# v0_1.net
KiCad netlist of a schematic drawn in EAGLE
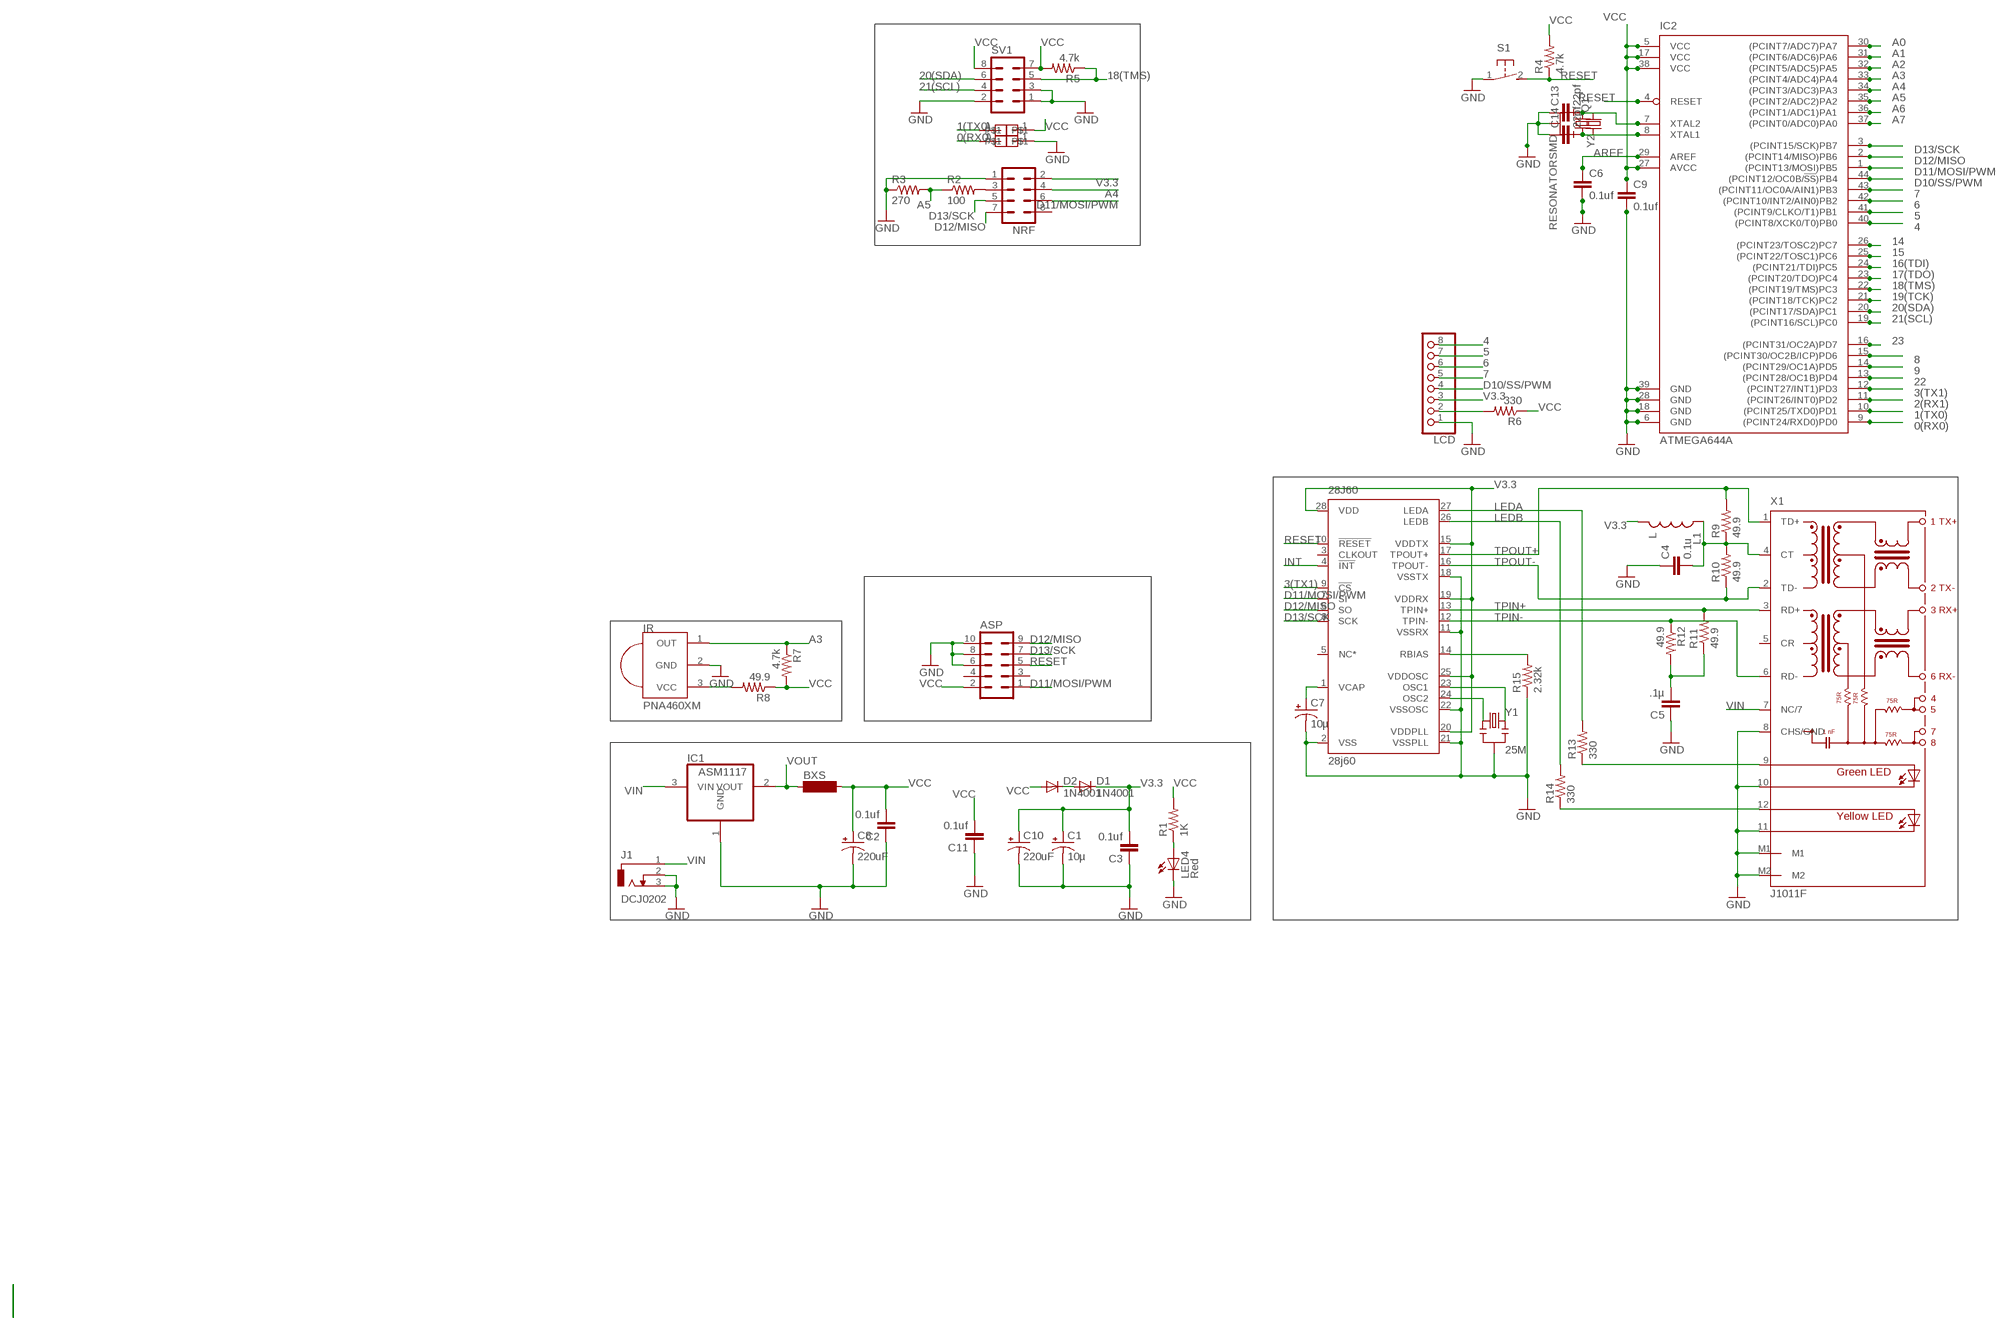
[diagram p0: schematic, sheet 1]

(export (version "E")
  (design (tool "Eeschema 10.0.6"))
  (components
    (comp (ref "28J60")
      (value "28j60")
      (footprint "eagle-import:SO28W")
      (libsource (lib "eagle-import") (part "ENC28J60SOIC"))
    )
    (comp (ref "ASP")
      (value "MA05-2")
      (footprint "eagle-import:MA05-2")
      (libsource (lib "eagle-import") (part "MA05-2"))
    )
    (comp (ref "BXS")
      (value "SM-1206")
      (footprint "eagle-import:SM-1206")
      (libsource (lib "eagle-import") (part "SM-1206"))
    )
    (comp (ref "C1")
      (value "10µ")
      (footprint "eagle-import:EIA3528")
      (libsource (lib "eagle-import") (part "CAP_POL3528"))
    )
    (comp (ref "C2")
      (value "0.1uf")
      (footprint "eagle-import:0603-CAP")
      (libsource (lib "eagle-import") (part "MY_CAP0603-CAP"))
    )
    (comp (ref "C3")
      (value "0.1uf")
      (footprint "eagle-import:0603-CAP")
      (libsource (lib "eagle-import") (part "MY_CAP0603-CAP"))
    )
    (comp (ref "C4")
      (value "0.1u")
      (footprint "eagle-import:0603-CAP")
      (libsource (lib "eagle-import") (part "CAP0603-CAP"))
    )
    (comp (ref "C5")
      (value ".1µ")
      (footprint "eagle-import:0603-CAP")
      (libsource (lib "eagle-import") (part "CAP0603-CAP"))
    )
    (comp (ref "C6")
      (value "0.1uf")
      (footprint "eagle-import:0603-CAP")
      (libsource (lib "eagle-import") (part "CAP0603-CAP"))
    )
    (comp (ref "C7")
      (value "10µ")
      (footprint "eagle-import:EIA3528")
      (libsource (lib "eagle-import") (part "CAP_POL3528"))
    )
    (comp (ref "C8")
      (value "220uF")
      (footprint "eagle-import:153CLV-0605")
      (libsource (lib "eagle-import") (part "CPOL-US153CLV-0605"))
    )
    (comp (ref "C9")
      (value "0.1uf")
      (footprint "eagle-import:0603-CAP")
      (libsource (lib "eagle-import") (part "CAP0603-CAP"))
    )
    (comp (ref "C10")
      (value "220uF")
      (footprint "eagle-import:153CLV-0605")
      (libsource (lib "eagle-import") (part "CPOL-US153CLV-0605"))
    )
    (comp (ref "C11")
      (value "0.1uf")
      (footprint "eagle-import:0603-CAP")
      (libsource (lib "eagle-import") (part "MY_CAP0603-CAP"))
    )
    (comp (ref "C13")
      (value "22pf")
      (footprint "eagle-import:0603-CAP")
      (libsource (lib "eagle-import") (part "CAP0603-CAP"))
    )
    (comp (ref "C14")
      (value "22pf")
      (footprint "eagle-import:0603-CAP")
      (libsource (lib "eagle-import") (part "CAP0603-CAP"))
    )
    (comp (ref "D1")
      (value "1N4001")
      (footprint "eagle-import:SOD-323")
      (libsource (lib "eagle-import") (part "DIODESOD"))
    )
    (comp (ref "D2")
      (value "1N4001")
      (footprint "eagle-import:SOD-323")
      (libsource (lib "eagle-import") (part "DIODESOD"))
    )
    (comp (ref "IC1")
      (value "ASM1117")
      (footprint "eagle-import:SOT223")
      (fields (field (name "MPN") "REG1117"))
      (libsource (lib "eagle-import") (part "REG1117"))
    )
    (comp (ref "IC2")
      (value "ATMEGA644A")
      (footprint "eagle-import:TQFP44")
      (fields (field (name "MPN") "ATMEGA644PV-10AU"))
      (libsource (lib "eagle-import") (part "ATMEGA644A"))
    )
    (comp (ref "IR")
      (value "PNA460XM")
      (footprint "eagle-import:PNA460XM")
      (libsource (lib "eagle-import") (part "PNA460XM"))
    )
    (comp (ref "J1")
      (value "DCJ0202")
      (footprint "eagle-import:DCJ0202")
      (libsource (lib "eagle-import") (part "DCJ0202"))
    )
    (comp (ref "L1")
      (value "L")
      (footprint "eagle-import:0603")
      (libsource (lib "eagle-import") (part "INDUCTOR0603"))
    )
    (comp (ref "LCD")
      (value "PINHD-1X8")
      (footprint "eagle-import:1X08")
      (libsource (lib "eagle-import") (part "PINHD-1X8"))
    )
    (comp (ref "LED4")
      (value "Red")
      (footprint "eagle-import:0805-LED")
      (libsource (lib "eagle-import") (part "LED0805"))
    )
    (comp (ref "NRF")
      (value "MA04-2")
      (footprint "eagle-import:MA04-2")
      (libsource (lib "eagle-import") (part "MA04-2"))
    )
    (comp (ref "Q1")
      (value "CRYSTALHC49S")
      (footprint "eagle-import:HC49_S")
      (libsource (lib "eagle-import") (part "CRYSTALHC49S"))
    )
    (comp (ref "R1")
      (value "1K")
      (footprint "eagle-import:0603-RES")
      (libsource (lib "eagle-import") (part "MY_RESISTOR0603-RES"))
    )
    (comp (ref "R2")
      (value "100")
      (footprint "eagle-import:0603-RES")
      (libsource (lib "eagle-import") (part "MY_RESISTOR0603-RES"))
    )
    (comp (ref "R3")
      (value "270")
      (footprint "eagle-import:0603-RES")
      (libsource (lib "eagle-import") (part "MY_RESISTOR0603-RES"))
    )
    (comp (ref "R4")
      (value "4.7k")
      (footprint "eagle-import:0603-RES")
      (libsource (lib "eagle-import") (part "RESISTOR0603-RES"))
    )
    (comp (ref "R5")
      (value "4.7k")
      (footprint "eagle-import:0603-RES")
      (libsource (lib "eagle-import") (part "MY_RESISTOR0603-RES"))
    )
    (comp (ref "R6")
      (value "330")
      (footprint "eagle-import:0603-RES")
      (libsource (lib "eagle-import") (part "MY_RESISTOR0603-RES"))
    )
    (comp (ref "R7")
      (value "4.7k")
      (footprint "eagle-import:0603-RES")
      (libsource (lib "eagle-import") (part "MY_RESISTOR0603-RES"))
    )
    (comp (ref "R8")
      (value "49.9")
      (footprint "eagle-import:0603-RES")
      (libsource (lib "eagle-import") (part "MY_RESISTOR0603-RES"))
    )
    (comp (ref "R9")
      (value "49.9")
      (footprint "eagle-import:0603-RES")
      (libsource (lib "eagle-import") (part "RESISTOR0603-RES"))
    )
    (comp (ref "R10")
      (value "49.9")
      (footprint "eagle-import:0603-RES")
      (libsource (lib "eagle-import") (part "RESISTOR0603-RES"))
    )
    (comp (ref "R11")
      (value "49.9")
      (footprint "eagle-import:0603-RES")
      (libsource (lib "eagle-import") (part "RESISTOR0603-RES"))
    )
    (comp (ref "R12")
      (value "49.9")
      (footprint "eagle-import:0603-RES")
      (libsource (lib "eagle-import") (part "RESISTOR0603-RES"))
    )
    (comp (ref "R13")
      (value "330")
      (footprint "eagle-import:0603-RES")
      (libsource (lib "eagle-import") (part "RESISTOR0603-RES"))
    )
    (comp (ref "R14")
      (value "330")
      (footprint "eagle-import:0603-RES")
      (libsource (lib "eagle-import") (part "RESISTOR0603-RES"))
    )
    (comp (ref "R15")
      (value "2.32k")
      (footprint "eagle-import:0603-RES")
      (libsource (lib "eagle-import") (part "RESISTOR0603-RES"))
    )
    (comp (ref "S1")
      (value "31-XX")
      (footprint "eagle-import:B3F-31XX")
      (fields (field (name "MPN") "B3F-3100"))
      (libsource (lib "eagle-import") (part "31-XX"))
    )
    (comp (ref "SV1")
      (value "MA04-2")
      (footprint "eagle-import:MA04-2")
      (libsource (lib "eagle-import") (part "MA04-2"))
    )
    (comp (ref "U$4")
      (value "PIN1")
      (footprint "eagle-import:PIN1")
      (libsource (lib "eagle-import") (part "PIN1"))
    )
    (comp (ref "U$5")
      (value "PIN1")
      (footprint "eagle-import:PIN1")
      (libsource (lib "eagle-import") (part "PIN1"))
    )
    (comp (ref "U$6")
      (value "PIN1")
      (footprint "eagle-import:PIN1")
      (libsource (lib "eagle-import") (part "PIN1"))
    )
    (comp (ref "U$7")
      (value "PIN1")
      (footprint "eagle-import:PIN1")
      (libsource (lib "eagle-import") (part "PIN1"))
    )
    (comp (ref "X1")
      (value "J1011F")
      (footprint "eagle-import:HRJ")
      (libsource (lib "eagle-import") (part "RJ45-HR911105A"))
    )
    (comp (ref "Y1")
      (value "25M")
      (footprint "eagle-import:RESONATOR-SMD")
      (libsource (lib "eagle-import") (part "RESONATORSMD"))
    )
    (comp (ref "Y2")
      (value "RESONATORSMD")
      (footprint "eagle-import:RESONATOR-SMD")
      (libsource (lib "eagle-import") (part "MY_RESONATORSMD"))
    )
  )
  (nets
    (net (code "1") (name "/0(RX0)") (class "Default")
      (node (ref "IC2") (pin "9") (pinfunction "(PCINT24/RXD0)PD0_9") (pintype "bidirectional"))
      (node (ref "U$7") (pin "1") (pinfunction "P$1_1") (pintype "bidirectional"))
    )
    (net (code "2") (name "/1(TX0)") (class "Default")
      (node (ref "IC2") (pin "10") (pinfunction "(PCINT25/TXD0)PD1_10") (pintype "bidirectional"))
      (node (ref "U$6") (pin "1") (pinfunction "P$1_1") (pintype "bidirectional"))
    )
    (net (code "3") (name "/2(RX1)") (class "Default")
      (node (ref "IC2") (pin "11") (pinfunction "(PCINT26/INT0)PD2_11") (pintype "bidirectional"))
    )
    (net (code "4") (name "/3(TX1)") (class "Default")
      (node (ref "28J60") (pin "9") (pinfunction "~{CS}_9") (pintype "input"))
      (node (ref "IC2") (pin "12") (pinfunction "(PCINT27/INT1)PD3_12") (pintype "bidirectional"))
    )
    (net (code "5") (name "/4") (class "Default")
      (node (ref "IC2") (pin "40") (pinfunction "(PCINT8/XCK0/T0)PB0_40") (pintype "bidirectional"))
      (node (ref "LCD") (pin "8") (pinfunction "8_8") (pintype "passive"))
    )
    (net (code "6") (name "/5") (class "Default")
      (node (ref "IC2") (pin "41") (pinfunction "(PCINT9/CLKO/T1)PB1_41") (pintype "bidirectional"))
      (node (ref "LCD") (pin "7") (pinfunction "7_7") (pintype "passive"))
    )
    (net (code "7") (name "/6") (class "Default")
      (node (ref "IC2") (pin "42") (pinfunction "(PCINT10/INT2/AIN0)PB2_42") (pintype "bidirectional"))
      (node (ref "LCD") (pin "6") (pinfunction "6_6") (pintype "passive"))
    )
    (net (code "8") (name "/7") (class "Default")
      (node (ref "IC2") (pin "43") (pinfunction "(PCINT11/OC0A/AIN1)PB3_43") (pintype "bidirectional"))
      (node (ref "LCD") (pin "5") (pinfunction "5_5") (pintype "passive"))
    )
    (net (code "9") (name "/8") (class "Default")
      (node (ref "IC2") (pin "15") (pinfunction "(PCINT30/OC2B/ICP)PD6_15") (pintype "bidirectional"))
    )
    (net (code "10") (name "/9") (class "Default")
      (node (ref "IC2") (pin "14") (pinfunction "(PCINT29/OC1A)PD5_14") (pintype "bidirectional"))
    )
    (net (code "11") (name "/14") (class "Default")
      (node (ref "IC2") (pin "26") (pinfunction "(PCINT23/TOSC2)PC7_26") (pintype "output"))
    )
    (net (code "12") (name "/15") (class "Default")
      (node (ref "IC2") (pin "25") (pinfunction "(PCINT22/TOSC1)PC6_25") (pintype "output"))
    )
    (net (code "13") (name "/16(TDI)") (class "Default")
      (node (ref "IC2") (pin "24") (pinfunction "(PCINT21/TDI)PC5_24") (pintype "output"))
    )
    (net (code "14") (name "/17(TDO)") (class "Default")
      (node (ref "IC2") (pin "23") (pinfunction "(PCINT20/TDO)PC4_23") (pintype "output"))
    )
    (net (code "15") (name "/18(TMS)") (class "Default")
      (node (ref "IC2") (pin "22") (pinfunction "(PCINT19/TMS)PC3_22") (pintype "output"))
      (node (ref "R5") (pin "1") (pinfunction "1_1") (pintype "passive"))
      (node (ref "SV1") (pin "5") (pinfunction "5_5") (pintype "passive"))
    )
    (net (code "16") (name "/19(TCK)") (class "Default")
      (node (ref "IC2") (pin "21") (pinfunction "(PCINT18/TCK)PC2_21") (pintype "output"))
    )
    (net (code "17") (name "/20(SDA)") (class "Default")
      (node (ref "IC2") (pin "20") (pinfunction "(PCINT17/SDA)PC1_20") (pintype "output"))
      (node (ref "SV1") (pin "6") (pinfunction "6_6") (pintype "passive"))
    )
    (net (code "18") (name "/21(SCL)") (class "Default")
      (node (ref "IC2") (pin "19") (pinfunction "(PCINT16/SCL)PC0_19") (pintype "output"))
      (node (ref "SV1") (pin "4") (pinfunction "4_4") (pintype "passive"))
    )
    (net (code "19") (name "/22") (class "Default")
      (node (ref "IC2") (pin "13") (pinfunction "(PCINT28/OC1B)PD4_13") (pintype "bidirectional"))
    )
    (net (code "20") (name "/23") (class "Default")
      (node (ref "IC2") (pin "16") (pinfunction "(PCINT31/OC2A)PD7_16") (pintype "bidirectional"))
    )
    (net (code "21") (name "/A0") (class "Default")
      (node (ref "IC2") (pin "30") (pinfunction "(PCINT7/ADC7)PA7_30") (pintype "bidirectional"))
    )
    (net (code "22") (name "/A1") (class "Default")
      (node (ref "IC2") (pin "31") (pinfunction "(PCINT6/ADC6)PA6_31") (pintype "bidirectional"))
    )
    (net (code "23") (name "/A2") (class "Default")
      (node (ref "IC2") (pin "32") (pinfunction "(PCINT5/ADC5)PA5_32") (pintype "bidirectional"))
    )
    (net (code "24") (name "/A3") (class "Default")
      (node (ref "IC2") (pin "33") (pinfunction "(PCINT4/ADC4)PA4_33") (pintype "bidirectional"))
      (node (ref "IR") (pin "1") (pinfunction "OUT_1") (pintype "output"))
      (node (ref "R7") (pin "1") (pinfunction "1_1") (pintype "passive"))
    )
    (net (code "25") (name "/A4") (class "Default")
      (node (ref "IC2") (pin "34") (pinfunction "(PCINT3/ADC3)PA3_34") (pintype "bidirectional"))
      (node (ref "NRF") (pin "4") (pinfunction "4_4") (pintype "passive"))
    )
    (net (code "26") (name "/A5") (class "Default")
      (node (ref "IC2") (pin "35") (pinfunction "(PCINT2/ADC2)PA2_35") (pintype "bidirectional"))
      (node (ref "R2") (pin "1") (pinfunction "1_1") (pintype "passive"))
      (node (ref "R3") (pin "2") (pinfunction "2_2") (pintype "passive"))
    )
    (net (code "27") (name "/A6") (class "Default")
      (node (ref "IC2") (pin "36") (pinfunction "(PCINT1/ADC1)PA1_36") (pintype "bidirectional"))
    )
    (net (code "28") (name "/A7") (class "Default")
      (node (ref "IC2") (pin "37") (pinfunction "(PCINT0/ADC0)PA0_37") (pintype "bidirectional"))
    )
    (net (code "29") (name "/AREF") (class "Default")
      (node (ref "C6") (pin "1") (pinfunction "1_1") (pintype "passive"))
      (node (ref "IC2") (pin "29") (pinfunction "AREF_29") (pintype "passive"))
    )
    (net (code "30") (name "/D10{slash}SS{slash}PWM") (class "Default")
      (node (ref "IC2") (pin "44") (pinfunction "(PCINT12/OC0B/~{SS})PB4_44") (pintype "bidirectional"))
      (node (ref "LCD") (pin "4") (pinfunction "4_4") (pintype "passive"))
    )
    (net (code "31") (name "/D11{slash}MOSI{slash}PWM") (class "Default")
      (node (ref "28J60") (pin "7") (pinfunction "SI_7") (pintype "input"))
      (node (ref "ASP") (pin "1") (pinfunction "1_1") (pintype "passive"))
      (node (ref "IC2") (pin "1") (pinfunction "(PCINT13/MOSI)PB5_1") (pintype "bidirectional"))
      (node (ref "NRF") (pin "6") (pinfunction "6_6") (pintype "passive"))
    )
    (net (code "32") (name "/D12{slash}MISO") (class "Default")
      (node (ref "28J60") (pin "6") (pinfunction "SO_6") (pintype "output"))
      (node (ref "ASP") (pin "9") (pinfunction "9_9") (pintype "passive"))
      (node (ref "IC2") (pin "2") (pinfunction "(PCINT14/MISO)PB6_2") (pintype "bidirectional"))
      (node (ref "NRF") (pin "7") (pinfunction "7_7") (pintype "passive"))
    )
    (net (code "33") (name "/D13{slash}SCK") (class "Default")
      (node (ref "28J60") (pin "8") (pinfunction "SCK_8") (pintype "input"))
      (node (ref "ASP") (pin "7") (pinfunction "7_7") (pintype "passive"))
      (node (ref "IC2") (pin "3") (pinfunction "(PCINT15/SCK)PB7_3") (pintype "bidirectional"))
      (node (ref "NRF") (pin "5") (pinfunction "5_5") (pintype "passive"))
    )
    (net (code "34") (name "/INT") (class "Default")
      (node (ref "28J60") (pin "4") (pinfunction "~{INT}_4") (pintype "output"))
    )
    (net (code "35") (name "/LEDA") (class "Default")
      (node (ref "28J60") (pin "27") (pinfunction "LEDA_27") (pintype "output"))
      (node (ref "R13") (pin "2") (pinfunction "2_2") (pintype "passive"))
    )
    (net (code "36") (name "/LEDB") (class "Default")
      (node (ref "28J60") (pin "26") (pinfunction "LEDB_26") (pintype "output"))
      (node (ref "R14") (pin "2") (pinfunction "2_2") (pintype "passive"))
    )
    (net (code "37") (name "/RESET") (class "Default")
      (node (ref "28J60") (pin "10") (pinfunction "~{RESET}_10") (pintype "input"))
      (node (ref "ASP") (pin "5") (pinfunction "5_5") (pintype "passive"))
      (node (ref "IC2") (pin "4") (pinfunction "RESET_4") (pintype "input"))
      (node (ref "R4") (pin "1") (pinfunction "1_1") (pintype "passive"))
      (node (ref "S1") (pin "2") (pinfunction "S_2") (pintype "passive"))
    )
    (net (code "38") (name "/TPIN+") (class "Default")
      (node (ref "28J60") (pin "13") (pinfunction "TPIN+_13") (pintype "input"))
      (node (ref "R11") (pin "2") (pinfunction "2_2") (pintype "passive"))
      (node (ref "X1") (pin "3") (pinfunction "RD+_3") (pintype "input"))
    )
    (net (code "39") (name "/TPIN-") (class "Default")
      (node (ref "28J60") (pin "12") (pinfunction "TPIN-_12") (pintype "input"))
      (node (ref "R12") (pin "1") (pinfunction "1_1") (pintype "passive"))
      (node (ref "X1") (pin "6") (pinfunction "RD-_6") (pintype "input"))
    )
    (net (code "40") (name "/TPOUT+") (class "Default")
      (node (ref "28J60") (pin "17") (pinfunction "TPOUT+_17") (pintype "output"))
      (node (ref "R9") (pin "2") (pinfunction "2_2") (pintype "passive"))
      (node (ref "X1") (pin "1") (pinfunction "TD+_1") (pintype "input"))
    )
    (net (code "41") (name "/TPOUT-") (class "Default")
      (node (ref "28J60") (pin "16") (pinfunction "TPOUT-_16") (pintype "output"))
      (node (ref "R10") (pin "1") (pinfunction "1_1") (pintype "passive"))
      (node (ref "X1") (pin "2") (pinfunction "TD-_2") (pintype "input"))
    )
    (net (code "42") (name "/V3.3") (class "Default")
      (node (ref "28J60") (pin "15") (pinfunction "VDDTX_15") (pintype "input"))
      (node (ref "28J60") (pin "19") (pinfunction "VDDRX_19") (pintype "input"))
      (node (ref "28J60") (pin "20") (pinfunction "VDDPLL_20") (pintype "input"))
      (node (ref "28J60") (pin "25") (pinfunction "VDDOSC_25") (pintype "input"))
      (node (ref "28J60") (pin "28") (pinfunction "VDD_28") (pintype "input"))
      (node (ref "C1") (pin "A") (pinfunction "+_A") (pintype "passive"))
      (node (ref "C10") (pin "+") (pinfunction "+_+") (pintype "passive"))
      (node (ref "C3") (pin "2") (pinfunction "2_2") (pintype "passive"))
      (node (ref "D1") (pin "1") (pinfunction "C_1") (pintype "passive"))
      (node (ref "L1") (pin "2") (pinfunction "2_2") (pintype "passive"))
      (node (ref "LCD") (pin "3") (pinfunction "3_3") (pintype "passive"))
      (node (ref "NRF") (pin "2") (pinfunction "2_2") (pintype "passive"))
    )
    (net (code "43") (name "/VCC") (class "Default")
      (node (ref "ASP") (pin "2") (pinfunction "2_2") (pintype "passive"))
      (node (ref "BXS") (pin "2") (pinfunction "2_2") (pintype "passive"))
      (node (ref "C11") (pin "2") (pinfunction "2_2") (pintype "passive"))
      (node (ref "C2") (pin "2") (pinfunction "2_2") (pintype "passive"))
      (node (ref "C8") (pin "+") (pinfunction "+_+") (pintype "passive"))
      (node (ref "C9") (pin "1") (pinfunction "1_1") (pintype "passive"))
      (node (ref "D2") (pin "2") (pinfunction "A_2") (pintype "passive"))
      (node (ref "IC2") (pin "17") (pinfunction "VCC_17") (pintype "power_in"))
      (node (ref "IC2") (pin "27") (pinfunction "AVCC_27") (pintype "power_in"))
      (node (ref "IC2") (pin "38") (pinfunction "VCC_38") (pintype "power_in"))
      (node (ref "IC2") (pin "5") (pinfunction "VCC_5") (pintype "power_in"))
      (node (ref "R1") (pin "2") (pinfunction "2_2") (pintype "passive"))
      (node (ref "R4") (pin "2") (pinfunction "2_2") (pintype "passive"))
      (node (ref "R5") (pin "2") (pinfunction "2_2") (pintype "passive"))
      (node (ref "R6") (pin "1") (pinfunction "1_1") (pintype "passive"))
      (node (ref "R7") (pin "2") (pinfunction "2_2") (pintype "passive"))
      (node (ref "R8") (pin "1") (pinfunction "1_1") (pintype "passive"))
      (node (ref "SV1") (pin "7") (pinfunction "7_7") (pintype "passive"))
      (node (ref "SV1") (pin "8") (pinfunction "8_8") (pintype "passive"))
      (node (ref "U$5") (pin "1") (pinfunction "P$1_1") (pintype "bidirectional"))
    )
    (net (code "44") (name "/VIN") (class "Default")
      (node (ref "IC1") (pin "3") (pinfunction "VIN_3") (pintype "input"))
      (node (ref "J1") (pin "1") (pinfunction "1_1") (pintype "passive"))
      (node (ref "X1") (pin "7") (pinfunction "NC/7_7") (pintype "input"))
    )
    (net (code "45") (name "/VOUT") (class "Default")
      (node (ref "BXS") (pin "1") (pinfunction "1_1") (pintype "passive"))
      (node (ref "IC1") (pin "2") (pinfunction "VOUT_2") (pintype "output"))
    )
    (net (code "46") (name "GND") (class "Default")
      (node (ref "28J60") (pin "11") (pinfunction "VSSRX_11") (pintype "input"))
      (node (ref "28J60") (pin "18") (pinfunction "VSSTX_18") (pintype "input"))
      (node (ref "28J60") (pin "2") (pinfunction "VSS_2") (pintype "input"))
      (node (ref "28J60") (pin "21") (pinfunction "VSSPLL_21") (pintype "input"))
      (node (ref "28J60") (pin "22") (pinfunction "VSSOSC_22") (pintype "input"))
      (node (ref "ASP") (pin "10") (pinfunction "10_10") (pintype "passive"))
      (node (ref "ASP") (pin "6") (pinfunction "6_6") (pintype "passive"))
      (node (ref "ASP") (pin "8") (pinfunction "8_8") (pintype "passive"))
      (node (ref "C1") (pin "C") (pinfunction "-_C") (pintype "passive"))
      (node (ref "C10") (pin "-") (pinfunction "-_-") (pintype "passive"))
      (node (ref "C11") (pin "1") (pinfunction "1_1") (pintype "passive"))
      (node (ref "C13") (pin "1") (pinfunction "1_1") (pintype "passive"))
      (node (ref "C14") (pin "1") (pinfunction "1_1") (pintype "passive"))
      (node (ref "C2") (pin "1") (pinfunction "1_1") (pintype "passive"))
      (node (ref "C3") (pin "1") (pinfunction "1_1") (pintype "passive"))
      (node (ref "C4") (pin "1") (pinfunction "1_1") (pintype "passive"))
      (node (ref "C5") (pin "1") (pinfunction "1_1") (pintype "passive"))
      (node (ref "C6") (pin "2") (pinfunction "2_2") (pintype "passive"))
      (node (ref "C7") (pin "C") (pinfunction "-_C") (pintype "passive"))
      (node (ref "C8") (pin "-") (pinfunction "-_-") (pintype "passive"))
      (node (ref "C9") (pin "2") (pinfunction "2_2") (pintype "passive"))
      (node (ref "IC1") (pin "1") (pinfunction "GND_1") (pintype "power_in"))
      (node (ref "IC2") (pin "18") (pinfunction "GND_18") (pintype "power_in"))
      (node (ref "IC2") (pin "28") (pinfunction "GND_28") (pintype "power_in"))
      (node (ref "IC2") (pin "39") (pinfunction "GND_39") (pintype "power_in"))
      (node (ref "IC2") (pin "6") (pinfunction "GND_6") (pintype "power_in"))
      (node (ref "IR") (pin "2") (pinfunction "GND_2") (pintype "power_in"))
      (node (ref "J1") (pin "2") (pinfunction "2_2") (pintype "passive"))
      (node (ref "J1") (pin "3") (pinfunction "3_3") (pintype "passive"))
      (node (ref "LCD") (pin "1") (pinfunction "1_1") (pintype "passive"))
      (node (ref "LED4") (pin "C") (pinfunction "C_C") (pintype "passive"))
      (node (ref "NRF") (pin "1") (pinfunction "1_1") (pintype "passive"))
      (node (ref "R15") (pin "1") (pinfunction "1_1") (pintype "passive"))
      (node (ref "R3") (pin "1") (pinfunction "1_1") (pintype "passive"))
      (node (ref "S1") (pin "1") (pinfunction "P_1") (pintype "passive"))
      (node (ref "SV1") (pin "1") (pinfunction "1_1") (pintype "passive"))
      (node (ref "SV1") (pin "2") (pinfunction "2_2") (pintype "passive"))
      (node (ref "SV1") (pin "3") (pinfunction "3_3") (pintype "passive"))
      (node (ref "U$4") (pin "1") (pinfunction "P$1_1") (pintype "bidirectional"))
      (node (ref "X1") (pin "10") (pinfunction "C-R_10") (pintype "passive"))
      (node (ref "X1") (pin "11") (pinfunction "C-L_11") (pintype "passive"))
      (node (ref "X1") (pin "8") (pinfunction "CHS/GND_8") (pintype "input"))
      (node (ref "X1") (pin "M1") (pinfunction "M1_M1") (pintype "bidirectional"))
      (node (ref "X1") (pin "M2") (pinfunction "M2_M2") (pintype "bidirectional"))
      (node (ref "Y1") (pin "2") (pinfunction "2_2") (pintype "passive"))
      (node (ref "Y2") (pin "2") (pinfunction "2_2") (pintype "passive"))
    )
    (net (code "47") (name "Net-(28J60-OSC1)") (class "Default")
      (node (ref "28J60") (pin "23") (pinfunction "OSC1_23") (pintype "input"))
      (node (ref "Y1") (pin "3") (pinfunction "3_3") (pintype "passive"))
    )
    (net (code "48") (name "Net-(28J60-OSC2)") (class "Default")
      (node (ref "28J60") (pin "24") (pinfunction "OSC2_24") (pintype "output"))
      (node (ref "Y1") (pin "1") (pinfunction "1_1") (pintype "passive"))
    )
    (net (code "49") (name "Net-(28J60-RBIAS)") (class "Default")
      (node (ref "28J60") (pin "14") (pinfunction "RBIAS_14") (pintype "input"))
      (node (ref "R15") (pin "2") (pinfunction "2_2") (pintype "passive"))
    )
    (net (code "50") (name "Net-(28J60-VCAP)") (class "Default")
      (node (ref "28J60") (pin "1") (pinfunction "VCAP_1") (pintype "input"))
      (node (ref "C7") (pin "A") (pinfunction "+_A") (pintype "passive"))
    )
    (net (code "51") (name "Net-(C5-Pad2)") (class "Default")
      (node (ref "C5") (pin "2") (pinfunction "2_2") (pintype "passive"))
      (node (ref "R11") (pin "1") (pinfunction "1_1") (pintype "passive"))
      (node (ref "R12") (pin "2") (pinfunction "2_2") (pintype "passive"))
    )
    (net (code "52") (name "Net-(D1-A)") (class "Default")
      (node (ref "D1") (pin "2") (pinfunction "A_2") (pintype "passive"))
      (node (ref "D2") (pin "1") (pinfunction "C_1") (pintype "passive"))
    )
    (net (code "53") (name "Net-(IC2-XTAL1)") (class "Default")
      (node (ref "C14") (pin "2") (pinfunction "2_2") (pintype "passive"))
      (node (ref "IC2") (pin "8") (pinfunction "XTAL1_8") (pintype "bidirectional"))
      (node (ref "Q1") (pin "1") (pinfunction "1_1") (pintype "passive"))
      (node (ref "Y2") (pin "3") (pinfunction "3_3") (pintype "passive"))
    )
    (net (code "54") (name "Net-(IC2-XTAL2)") (class "Default")
      (node (ref "C13") (pin "2") (pinfunction "2_2") (pintype "passive"))
      (node (ref "IC2") (pin "7") (pinfunction "XTAL2_7") (pintype "bidirectional"))
      (node (ref "Q1") (pin "2") (pinfunction "2_2") (pintype "passive"))
      (node (ref "Y2") (pin "1") (pinfunction "1_1") (pintype "passive"))
    )
    (net (code "55") (name "Net-(IR-VCC)") (class "Default")
      (node (ref "IR") (pin "3") (pinfunction "VCC_3") (pintype "power_in"))
      (node (ref "R8") (pin "2") (pinfunction "2_2") (pintype "passive"))
    )
    (net (code "56") (name "Net-(LCD-Pad2)") (class "Default")
      (node (ref "LCD") (pin "2") (pinfunction "2_2") (pintype "passive"))
      (node (ref "R6") (pin "2") (pinfunction "2_2") (pintype "passive"))
    )
    (net (code "57") (name "Net-(LED4-PadA)") (class "Default")
      (node (ref "LED4") (pin "A") (pinfunction "A_A") (pintype "passive"))
      (node (ref "R1") (pin "1") (pinfunction "1_1") (pintype "passive"))
    )
    (net (code "58") (name "Net-(NRF-Pad3)") (class "Default")
      (node (ref "NRF") (pin "3") (pinfunction "3_3") (pintype "passive"))
      (node (ref "R2") (pin "2") (pinfunction "2_2") (pintype "passive"))
    )
    (net (code "59") (name "Net-(X1-A-R)") (class "Default")
      (node (ref "R13") (pin "1") (pinfunction "1_1") (pintype "passive"))
      (node (ref "X1") (pin "9") (pinfunction "A-R_9") (pintype "passive"))
    )
    (net (code "60") (name "Net-(X1-AL)") (class "Default")
      (node (ref "R14") (pin "1") (pinfunction "1_1") (pintype "passive"))
      (node (ref "X1") (pin "12") (pinfunction "AL_12") (pintype "passive"))
    )
    (net (code "61") (name "Net-(X1-CT)") (class "Default")
      (node (ref "C4") (pin "2") (pinfunction "2_2") (pintype "passive"))
      (node (ref "L1") (pin "1") (pinfunction "1_1") (pintype "passive"))
      (node (ref "R10") (pin "2") (pinfunction "2_2") (pintype "passive"))
      (node (ref "R9") (pin "1") (pinfunction "1_1") (pintype "passive"))
      (node (ref "X1") (pin "4") (pinfunction "CT_4") (pintype "input"))
    )
    (net (code "62") (name "unconnected-(28J60-CLKOUT-Pad3)") (class "Default")
      (node (ref "28J60") (pin "3") (pinfunction "CLKOUT_3") (pintype "output"))
    )
    (net (code "63") (name "unconnected-(28J60-NC*-Pad5)") (class "Default")
      (node (ref "28J60") (pin "5") (pinfunction "NC*_5") (pintype "output"))
    )
    (net (code "64") (name "unconnected-(ASP-Pad3)") (class "Default")
      (node (ref "ASP") (pin "3") (pinfunction "3_3") (pintype "passive"))
    )
    (net (code "65") (name "unconnected-(ASP-Pad4)") (class "Default")
      (node (ref "ASP") (pin "4") (pinfunction "4_4") (pintype "passive"))
    )
    (net (code "66") (name "unconnected-(NRF-Pad8)") (class "Default")
      (node (ref "NRF") (pin "8") (pinfunction "8_8") (pintype "passive"))
    )
    (net (code "67") (name "unconnected-(X1-CR-Pad5)") (class "Default")
      (node (ref "X1") (pin "5") (pinfunction "CR_5") (pintype "input"))
    )
  )
)
